# daughter_board_V1.net
KiCad netlist of a schematic drawn in EAGLE
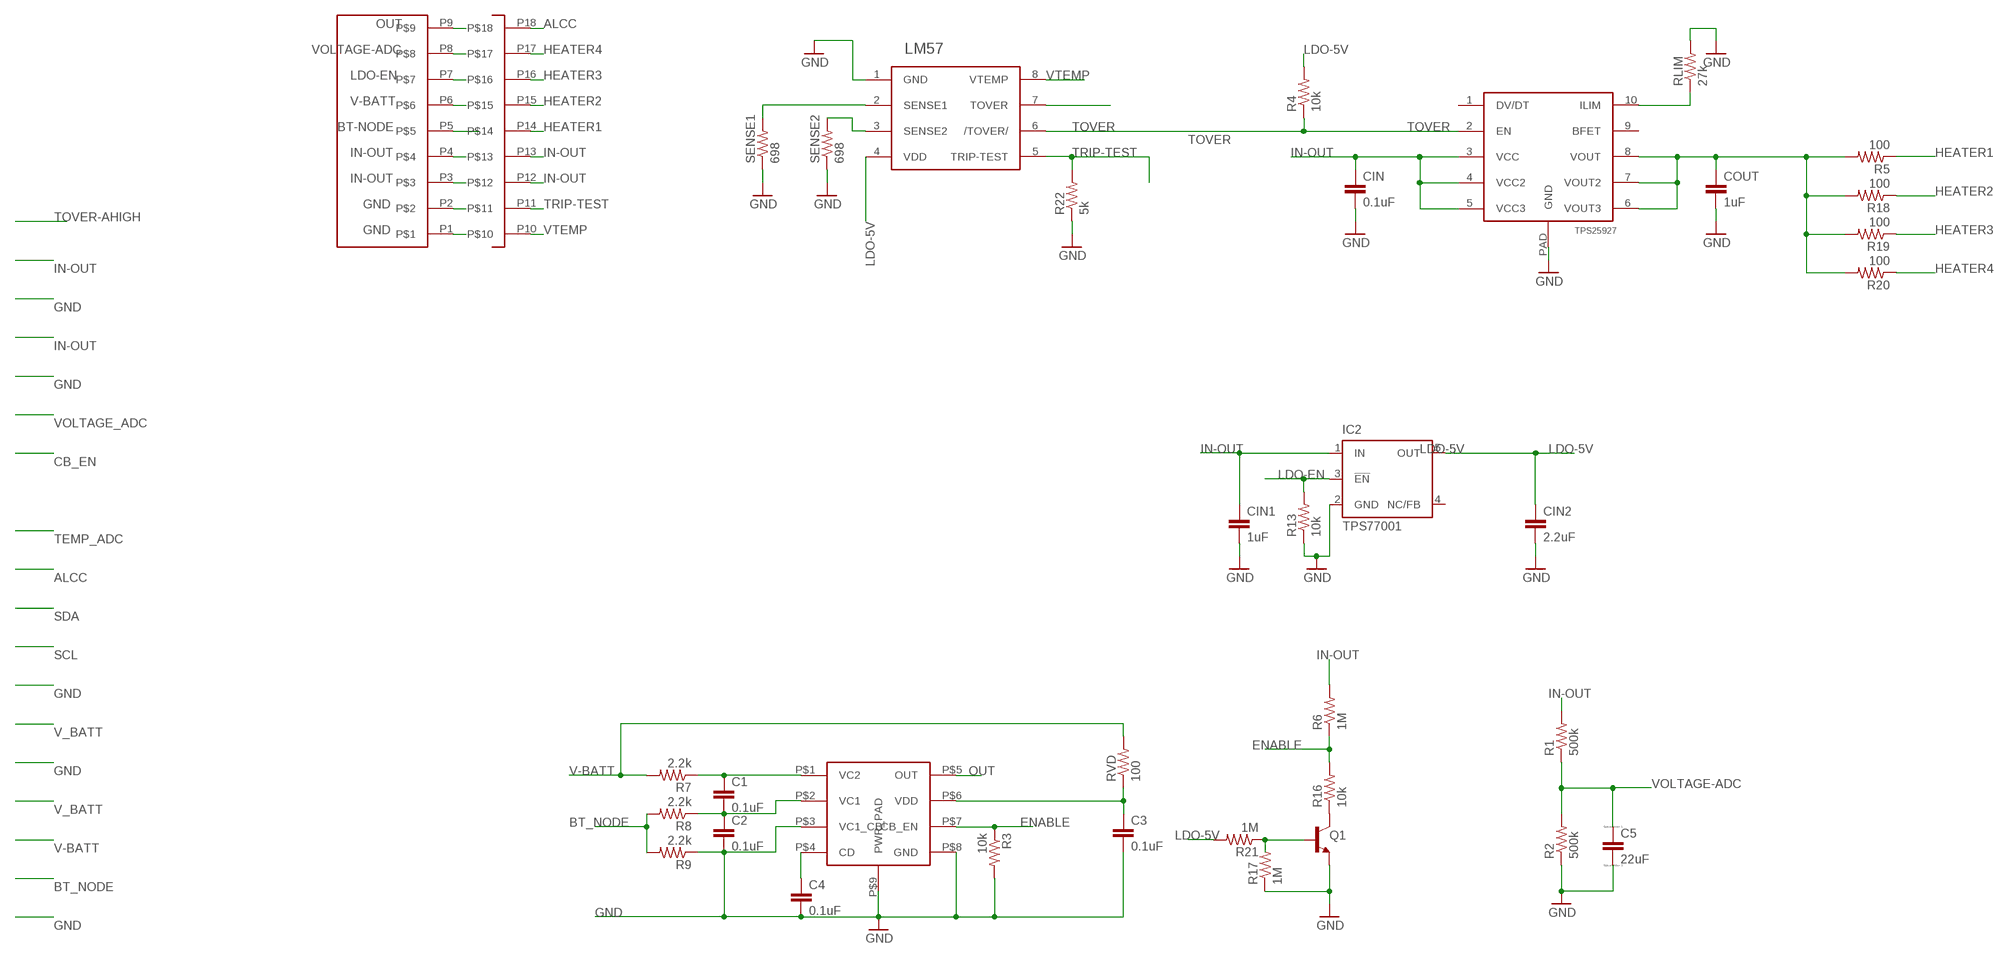
[diagram p0: schematic, sheet 1]

(export (version "E")
  (design (tool "Eeschema 10.0.6"))
  (components
    (comp (ref "C1")
      (value "0.1uF")
      (footprint "eagle-import:0402-CAP")
      (libsource (lib "eagle-import") (part ".1UF-CER"))
    )
    (comp (ref "C2")
      (value "0.1uF")
      (footprint "eagle-import:0402-CAP")
      (libsource (lib "eagle-import") (part ".1UF-CER"))
    )
    (comp (ref "C3")
      (value "0.1uF")
      (footprint "eagle-import:0402-CAP")
      (libsource (lib "eagle-import") (part ".1UF-CER"))
    )
    (comp (ref "C4")
      (value "0.1uF")
      (footprint "eagle-import:0402-CAP")
      (libsource (lib "eagle-import") (part ".1UF-CER"))
    )
    (comp (ref "C5")
      (value "22uF")
      (footprint "eagle-import:C1206")
      (libsource (lib "eagle-import") (part "CC1206"))
    )
    (comp (ref "CIN")
      (value "0.1uF")
      (footprint "eagle-import:0402-CAP")
      (libsource (lib "eagle-import") (part ".1UF-CER"))
    )
    (comp (ref "CIN1")
      (value "1uF")
      (footprint "eagle-import:0402-CAP")
      (libsource (lib "eagle-import") (part ".1UF-CER"))
    )
    (comp (ref "CIN2")
      (value "2.2uF")
      (footprint "eagle-import:0402-CAP")
      (libsource (lib "eagle-import") (part ".1UF-CER"))
    )
    (comp (ref "COUT")
      (value "1uF")
      (footprint "eagle-import:0402-CAP")
      (libsource (lib "eagle-import") (part ".1UF-CER"))
    )
    (comp (ref "IC2")
      (value "TPS77001")
      (footprint "eagle-import:SOT23-DBV")
      (fields (field (name "MF") "TEXAS INSTRUMENTS") (field (name "MPN") "TPS77001DBVT"))
      (libsource (lib "eagle-import") (part "TPS77001"))
    )
    (comp (ref "Q1")
      (value "TRANS_NPN-MMBT2222AL")
      (footprint "eagle-import:SOT23-3")
      (libsource (lib "eagle-import") (part "TRANS_NPN-MMBT2222AL"))
    )
    (comp (ref "R1")
      (value "500k")
      (footprint "eagle-import:R0805")
      (libsource (lib "eagle-import") (part "R-US_R0805"))
    )
    (comp (ref "R2")
      (value "500k")
      (footprint "eagle-import:R0805")
      (libsource (lib "eagle-import") (part "R-US_R0805"))
    )
    (comp (ref "R3")
      (value "10k")
      (footprint "eagle-import:R0805")
      (libsource (lib "eagle-import") (part "R-US_R0805"))
    )
    (comp (ref "R4")
      (value "10k")
      (footprint "eagle-import:R0805")
      (libsource (lib "eagle-import") (part "R-US_R0805"))
    )
    (comp (ref "R5")
      (value "100")
      (footprint "eagle-import:R0805")
      (libsource (lib "eagle-import") (part "R-US_R0805"))
    )
    (comp (ref "R6")
      (value "1M")
      (footprint "eagle-import:R0805")
      (libsource (lib "eagle-import") (part "R-US_R0805"))
    )
    (comp (ref "R7")
      (value "2.2k")
      (footprint "eagle-import:R0805")
      (libsource (lib "eagle-import") (part "R-US_R0805"))
    )
    (comp (ref "R8")
      (value "2.2k")
      (footprint "eagle-import:R0805")
      (libsource (lib "eagle-import") (part "R-US_R0805"))
    )
    (comp (ref "R9")
      (value "2.2k")
      (footprint "eagle-import:R0805")
      (libsource (lib "eagle-import") (part "R-US_R0805"))
    )
    (comp (ref "R13")
      (value "10k")
      (footprint "eagle-import:R0805")
      (libsource (lib "eagle-import") (part "R-US_R0805"))
    )
    (comp (ref "R16")
      (value "10k")
      (footprint "eagle-import:R0805")
      (libsource (lib "eagle-import") (part "R-US_R0805"))
    )
    (comp (ref "R17")
      (value "1M")
      (footprint "eagle-import:M0805")
      (libsource (lib "eagle-import") (part "R-US_M0805"))
    )
    (comp (ref "R18")
      (value "100")
      (footprint "eagle-import:R0805")
      (libsource (lib "eagle-import") (part "R-US_R0805"))
    )
    (comp (ref "R19")
      (value "100")
      (footprint "eagle-import:R0805")
      (libsource (lib "eagle-import") (part "R-US_R0805"))
    )
    (comp (ref "R20")
      (value "100")
      (footprint "eagle-import:R0805")
      (libsource (lib "eagle-import") (part "R-US_R0805"))
    )
    (comp (ref "R21")
      (value "1M")
      (footprint "eagle-import:M0805")
      (libsource (lib "eagle-import") (part "R-US_M0805"))
    )
    (comp (ref "R22")
      (value "5k")
      (footprint "eagle-import:R0805")
      (libsource (lib "eagle-import") (part "R-US_R0805"))
    )
    (comp (ref "RLIM")
      (value "27k")
      (footprint "eagle-import:R0805")
      (libsource (lib "eagle-import") (part "R-US_R0805"))
    )
    (comp (ref "RVD")
      (value "100")
      (footprint "eagle-import:R0805")
      (libsource (lib "eagle-import") (part "R-US_R0805"))
    )
    (comp (ref "SENSE1")
      (value "698")
      (footprint "eagle-import:R0805")
      (libsource (lib "eagle-import") (part "R-US_R0805"))
    )
    (comp (ref "SENSE2")
      (value "698")
      (footprint "eagle-import:R0805")
      (libsource (lib "eagle-import") (part "R-US_R0805"))
    )
    (comp (ref "U$2")
      (value "LM57")
      (footprint "eagle-import:TSSOP-8")
      (libsource (lib "eagle-import") (part "LM57"))
    )
    (comp (ref "U$5")
      (value "TPS252927")
      (footprint "eagle-import:VSON10")
      (libsource (lib "eagle-import") (part "TPS252927"))
    )
    (comp (ref "U$7")
      (value "FFC18")
      (footprint "eagle-import:FFC18")
      (libsource (lib "eagle-import") (part "FFC18"))
    )
    (comp (ref "U$8")
      (value "BQ29209")
      (footprint "eagle-import:VSON8")
      (libsource (lib "eagle-import") (part "BQ29209"))
    )
  )
  (nets
    (net (code "1") (name "/ALCC") (class "Default")
      (node (ref "U$7") (pin "P18") (pinfunction "P$18_P18") (pintype "bidirectional"))
    )
    (net (code "2") (name "/BT-NODE") (class "Default")
      (node (ref "U$7") (pin "P5") (pinfunction "P$5_P5") (pintype "bidirectional"))
    )
    (net (code "3") (name "/BT_NODE") (class "Default")
      (node (ref "R8") (pin "2") (pinfunction "2_2") (pintype "passive"))
      (node (ref "R9") (pin "2") (pinfunction "2_2") (pintype "passive"))
    )
    (net (code "5") (name "/ENABLE") (class "Default")
      (node (ref "R16") (pin "2") (pinfunction "2_2") (pintype "passive"))
      (node (ref "R3") (pin "1") (pinfunction "1_1") (pintype "passive"))
      (node (ref "R6") (pin "1") (pinfunction "1_1") (pintype "passive"))
      (node (ref "U$8") (pin "P$7") (pinfunction "CB_EN_P$7") (pintype "bidirectional"))
    )
    (net (code "6") (name "/HEATER1") (class "Default")
      (node (ref "R5") (pin "1") (pinfunction "1_1") (pintype "passive"))
      (node (ref "U$7") (pin "P14") (pinfunction "P$14_P14") (pintype "bidirectional"))
    )
    (net (code "7") (name "/HEATER2") (class "Default")
      (node (ref "R18") (pin "1") (pinfunction "1_1") (pintype "passive"))
      (node (ref "U$7") (pin "P15") (pinfunction "P$15_P15") (pintype "bidirectional"))
    )
    (net (code "8") (name "/HEATER3") (class "Default")
      (node (ref "R19") (pin "1") (pinfunction "1_1") (pintype "passive"))
      (node (ref "U$7") (pin "P16") (pinfunction "P$16_P16") (pintype "bidirectional"))
    )
    (net (code "9") (name "/HEATER4") (class "Default")
      (node (ref "R20") (pin "1") (pinfunction "1_1") (pintype "passive"))
      (node (ref "U$7") (pin "P17") (pinfunction "P$17_P17") (pintype "bidirectional"))
    )
    (net (code "10") (name "/IN-OUT") (class "Default")
      (node (ref "CIN") (pin "1") (pinfunction "1_1") (pintype "passive"))
      (node (ref "CIN1") (pin "1") (pinfunction "1_1") (pintype "passive"))
      (node (ref "IC2") (pin "1") (pinfunction "IN_1") (pintype "input"))
      (node (ref "R1") (pin "2") (pinfunction "2_2") (pintype "passive"))
      (node (ref "R6") (pin "2") (pinfunction "2_2") (pintype "passive"))
      (node (ref "U$5") (pin "3") (pinfunction "VCC_3") (pintype "bidirectional"))
      (node (ref "U$5") (pin "4") (pinfunction "VCC2_4") (pintype "bidirectional"))
      (node (ref "U$5") (pin "5") (pinfunction "VCC3_5") (pintype "bidirectional"))
      (node (ref "U$7") (pin "P12") (pinfunction "P$12_P12") (pintype "bidirectional"))
      (node (ref "U$7") (pin "P13") (pinfunction "P$13_P13") (pintype "bidirectional"))
      (node (ref "U$7") (pin "P3") (pinfunction "P$3_P3") (pintype "bidirectional"))
      (node (ref "U$7") (pin "P4") (pinfunction "P$4_P4") (pintype "bidirectional"))
    )
    (net (code "11") (name "/LDO-5V") (class "Default")
      (node (ref "CIN2") (pin "1") (pinfunction "1_1") (pintype "passive"))
      (node (ref "IC2") (pin "5") (pinfunction "OUT_5") (pintype "passive"))
      (node (ref "R21") (pin "2") (pinfunction "2_2") (pintype "passive"))
      (node (ref "R4") (pin "2") (pinfunction "2_2") (pintype "passive"))
      (node (ref "U$2") (pin "4") (pinfunction "VDD_4") (pintype "bidirectional"))
    )
    (net (code "12") (name "/LDO-EN") (class "Default")
      (node (ref "IC2") (pin "3") (pinfunction "~{EN}_3") (pintype "input"))
      (node (ref "R13") (pin "2") (pinfunction "2_2") (pintype "passive"))
      (node (ref "U$7") (pin "P7") (pinfunction "P$7_P7") (pintype "bidirectional"))
    )
    (net (code "13") (name "/OUT") (class "Default")
      (node (ref "U$7") (pin "P9") (pinfunction "P$9_P9") (pintype "bidirectional"))
      (node (ref "U$8") (pin "P$5") (pinfunction "OUT_P$5") (pintype "bidirectional"))
    )
    (net (code "17") (name "/TOVER") (class "Default")
      (node (ref "R4") (pin "1") (pinfunction "1_1") (pintype "passive"))
      (node (ref "U$2") (pin "6") (pinfunction "/TOVER/_6") (pintype "bidirectional"))
      (node (ref "U$5") (pin "2") (pinfunction "EN_2") (pintype "bidirectional"))
    )
    (net (code "19") (name "/TRIP-TEST") (class "Default")
      (node (ref "R22") (pin "2") (pinfunction "2_2") (pintype "passive"))
      (node (ref "U$2") (pin "5") (pinfunction "TRIP-TEST_5") (pintype "bidirectional"))
      (node (ref "U$7") (pin "P11") (pinfunction "P$11_P11") (pintype "bidirectional"))
    )
    (net (code "20") (name "/V-BATT") (class "Default")
      (node (ref "R7") (pin "2") (pinfunction "2_2") (pintype "passive"))
      (node (ref "RVD") (pin "2") (pinfunction "2_2") (pintype "passive"))
      (node (ref "U$7") (pin "P6") (pinfunction "P$6_P6") (pintype "bidirectional"))
    )
    (net (code "21") (name "/VOLTAGE-ADC") (class "Default")
      (node (ref "C5") (pin "1") (pinfunction "1_1") (pintype "passive"))
      (node (ref "R1") (pin "1") (pinfunction "1_1") (pintype "passive"))
      (node (ref "R2") (pin "2") (pinfunction "2_2") (pintype "passive"))
      (node (ref "U$7") (pin "P8") (pinfunction "P$8_P8") (pintype "bidirectional"))
    )
    (net (code "23") (name "/VTEMP") (class "Default")
      (node (ref "U$2") (pin "8") (pinfunction "VTEMP_8") (pintype "bidirectional"))
      (node (ref "U$7") (pin "P10") (pinfunction "P$10_P10") (pintype "bidirectional"))
    )
    (net (code "25") (name "GND") (class "Default")
      (node (ref "C2") (pin "2") (pinfunction "2_2") (pintype "passive"))
      (node (ref "C3") (pin "2") (pinfunction "2_2") (pintype "passive"))
      (node (ref "C4") (pin "2") (pinfunction "2_2") (pintype "passive"))
      (node (ref "C5") (pin "2") (pinfunction "2_2") (pintype "passive"))
      (node (ref "CIN") (pin "2") (pinfunction "2_2") (pintype "passive"))
      (node (ref "CIN1") (pin "2") (pinfunction "2_2") (pintype "passive"))
      (node (ref "CIN2") (pin "2") (pinfunction "2_2") (pintype "passive"))
      (node (ref "COUT") (pin "2") (pinfunction "2_2") (pintype "passive"))
      (node (ref "IC2") (pin "2") (pinfunction "GND_2") (pintype "power_in"))
      (node (ref "Q1") (pin "2") (pinfunction "E_2") (pintype "passive"))
      (node (ref "R13") (pin "1") (pinfunction "1_1") (pintype "passive"))
      (node (ref "R17") (pin "1") (pinfunction "1_1") (pintype "passive"))
      (node (ref "R2") (pin "1") (pinfunction "1_1") (pintype "passive"))
      (node (ref "R22") (pin "1") (pinfunction "1_1") (pintype "passive"))
      (node (ref "R3") (pin "2") (pinfunction "2_2") (pintype "passive"))
      (node (ref "R9") (pin "1") (pinfunction "1_1") (pintype "passive"))
      (node (ref "RLIM") (pin "2") (pinfunction "2_2") (pintype "passive"))
      (node (ref "SENSE1") (pin "1") (pinfunction "1_1") (pintype "passive"))
      (node (ref "SENSE2") (pin "1") (pinfunction "1_1") (pintype "passive"))
      (node (ref "U$2") (pin "1") (pinfunction "GND_1") (pintype "bidirectional"))
      (node (ref "U$5") (pin "PAD") (pinfunction "GND_PAD") (pintype "bidirectional"))
      (node (ref "U$7") (pin "P1") (pinfunction "P$1_P1") (pintype "bidirectional"))
      (node (ref "U$7") (pin "P2") (pinfunction "P$2_P2") (pintype "bidirectional"))
      (node (ref "U$8") (pin "P$3") (pinfunction "VC1_CB_P$3") (pintype "bidirectional"))
      (node (ref "U$8") (pin "P$8") (pinfunction "GND_P$8") (pintype "bidirectional"))
      (node (ref "U$8") (pin "P$9") (pinfunction "PWR_PAD_P$9") (pintype "bidirectional"))
    )
    (net (code "26") (name "Net-(Q1-B)") (class "Default")
      (node (ref "Q1") (pin "1") (pinfunction "B_1") (pintype "passive"))
      (node (ref "R17") (pin "2") (pinfunction "2_2") (pintype "passive"))
      (node (ref "R21") (pin "1") (pinfunction "1_1") (pintype "passive"))
    )
    (net (code "27") (name "Net-(Q1-C)") (class "Default")
      (node (ref "Q1") (pin "3") (pinfunction "C_3") (pintype "passive"))
      (node (ref "R16") (pin "1") (pinfunction "1_1") (pintype "passive"))
    )
    (net (code "28") (name "Net-(U$2-SENSE1)") (class "Default")
      (node (ref "SENSE1") (pin "2") (pinfunction "2_2") (pintype "passive"))
      (node (ref "U$2") (pin "2") (pinfunction "SENSE1_2") (pintype "bidirectional"))
    )
    (net (code "29") (name "Net-(U$2-SENSE2)") (class "Default")
      (node (ref "SENSE2") (pin "2") (pinfunction "2_2") (pintype "passive"))
      (node (ref "U$2") (pin "3") (pinfunction "SENSE2_3") (pintype "bidirectional"))
    )
    (net (code "30") (name "Net-(U$5-ILIM)") (class "Default")
      (node (ref "RLIM") (pin "1") (pinfunction "1_1") (pintype "passive"))
      (node (ref "U$5") (pin "10") (pinfunction "ILIM_10") (pintype "bidirectional"))
    )
    (net (code "31") (name "Net-(U$5-VOUT)") (class "Default")
      (node (ref "COUT") (pin "1") (pinfunction "1_1") (pintype "passive"))
      (node (ref "R18") (pin "2") (pinfunction "2_2") (pintype "passive"))
      (node (ref "R19") (pin "2") (pinfunction "2_2") (pintype "passive"))
      (node (ref "R20") (pin "2") (pinfunction "2_2") (pintype "passive"))
      (node (ref "R5") (pin "2") (pinfunction "2_2") (pintype "passive"))
      (node (ref "U$5") (pin "6") (pinfunction "VOUT3_6") (pintype "bidirectional"))
      (node (ref "U$5") (pin "7") (pinfunction "VOUT2_7") (pintype "bidirectional"))
      (node (ref "U$5") (pin "8") (pinfunction "VOUT_8") (pintype "bidirectional"))
    )
    (net (code "32") (name "Net-(U$8-CD)") (class "Default")
      (node (ref "C4") (pin "1") (pinfunction "1_1") (pintype "passive"))
      (node (ref "U$8") (pin "P$4") (pinfunction "CD_P$4") (pintype "bidirectional"))
    )
    (net (code "33") (name "Net-(U$8-VC1)") (class "Default")
      (node (ref "C1") (pin "2") (pinfunction "2_2") (pintype "passive"))
      (node (ref "C2") (pin "1") (pinfunction "1_1") (pintype "passive"))
      (node (ref "R8") (pin "1") (pinfunction "1_1") (pintype "passive"))
      (node (ref "U$8") (pin "P$2") (pinfunction "VC1_P$2") (pintype "bidirectional"))
    )
    (net (code "34") (name "Net-(U$8-VC2)") (class "Default")
      (node (ref "C1") (pin "1") (pinfunction "1_1") (pintype "passive"))
      (node (ref "R7") (pin "1") (pinfunction "1_1") (pintype "passive"))
      (node (ref "U$8") (pin "P$1") (pinfunction "VC2_P$1") (pintype "bidirectional"))
    )
    (net (code "35") (name "Net-(U$8-VDD)") (class "Default")
      (node (ref "C3") (pin "1") (pinfunction "1_1") (pintype "passive"))
      (node (ref "RVD") (pin "1") (pinfunction "1_1") (pintype "passive"))
      (node (ref "U$8") (pin "P$6") (pinfunction "VDD_P$6") (pintype "bidirectional"))
    )
    (net (code "36") (name "unconnected-(IC2-NC{slash}FB-Pad4)") (class "Default")
      (node (ref "IC2") (pin "4") (pinfunction "NC/FB_4") (pintype "passive"))
    )
    (net (code "37") (name "unconnected-(U$2-TOVER-Pad7)") (class "Default")
      (node (ref "U$2") (pin "7") (pinfunction "TOVER_7") (pintype "bidirectional"))
    )
    (net (code "38") (name "unconnected-(U$5-BFET-Pad9)") (class "Default")
      (node (ref "U$5") (pin "9") (pinfunction "BFET_9") (pintype "bidirectional"))
    )
    (net (code "39") (name "unconnected-(U$5-DV{slash}DT-Pad1)") (class "Default")
      (node (ref "U$5") (pin "1") (pinfunction "DV/DT_1") (pintype "bidirectional"))
    )
  )
)
